# shield.net
KiCad netlist of a schematic drawn in EAGLE
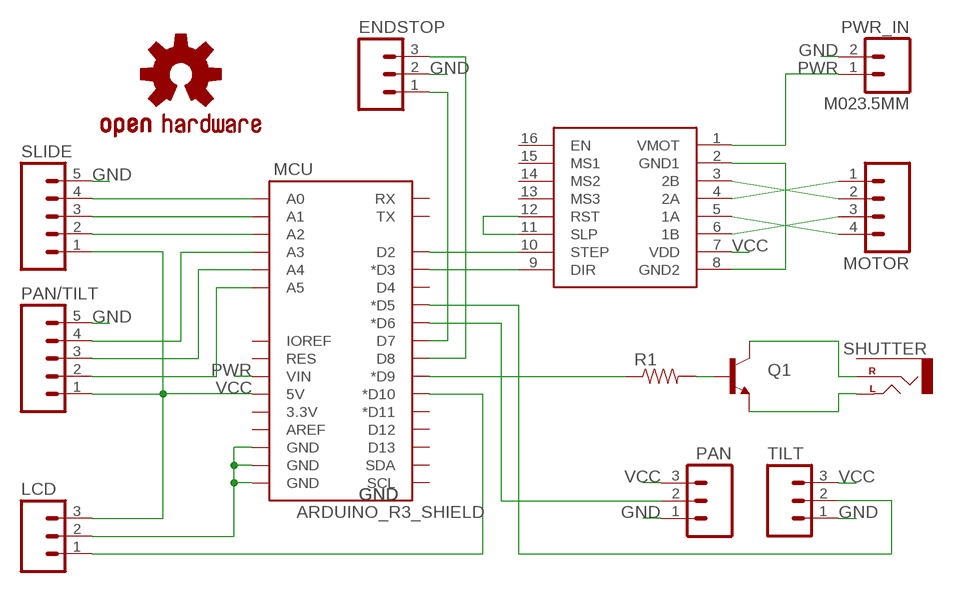
[diagram p0: schematic, sheet 1]

(export (version "E")
  (design (tool "Eeschema 10.0.6"))
  (components
    (comp (ref "ENDSTOP")
      (value "M03PTH")
      (footprint "eagle-import:1X03")
      (libsource (lib "eagle-import") (part "M03PTH"))
    )
    (comp (ref "LCD")
      (value "M03PTH")
      (footprint "eagle-import:1X03")
      (libsource (lib "eagle-import") (part "M03PTH"))
    )
    (comp (ref "LOGO1")
      (value "OSHW-LOGOM")
      (footprint "eagle-import:OSHW-LOGO-M")
      (libsource (lib "eagle-import") (part "OSHW-LOGOM"))
    )
    (comp (ref "MCU")
      (value "ARDUINO_R3_SHIELD")
      (footprint "eagle-import:UNO_R3_SHIELD")
      (libsource (lib "eagle-import") (part "ARDUINO_R3_SHIELD"))
    )
    (comp (ref "MOTOR")
      (value "M04POLAR")
      (footprint "eagle-import:MOLEX-1X4")
      (libsource (lib "eagle-import") (part "M04POLAR"))
    )
    (comp (ref "PAN")
      (value "M03PTH")
      (footprint "eagle-import:1X03")
      (libsource (lib "eagle-import") (part "M03PTH"))
    )
    (comp (ref "PAN/TILT")
      (value "M05PTH")
      (footprint "eagle-import:1X05")
      (libsource (lib "eagle-import") (part "M05PTH"))
    )
    (comp (ref "PWR_IN")
      (value "M023.5MM")
      (footprint "eagle-import:SCREWTERMINAL-3.5MM-2")
      (libsource (lib "eagle-import") (part "M023.5MM"))
    )
    (comp (ref "Q1")
      (value "TRANSISTOR_NPN2N3904")
      (footprint "eagle-import:TO-92")
      (libsource (lib "eagle-import") (part "TRANSISTOR_NPN2N3904"))
    )
    (comp (ref "R1")
      (value "RESISTORAXIAL-0.3")
      (footprint "eagle-import:AXIAL-0.3")
      (libsource (lib "eagle-import") (part "RESISTORAXIAL-0.3"))
    )
    (comp (ref "SHUTTER")
      (value "AUDIO-JACKPTH")
      (footprint "eagle-import:AUDIO-JACK")
      (libsource (lib "eagle-import") (part "AUDIO-JACKPTH"))
    )
    (comp (ref "SLIDE")
      (value "M05PTH")
      (footprint "eagle-import:1X05")
      (libsource (lib "eagle-import") (part "M05PTH"))
    )
    (comp (ref "SOCKET")
      (value "POLOLU DRIVER")
      (footprint "eagle-import:DIL16")
      (libsource (lib "eagle-import") (part "POLOLUESTEPPERDRIVER"))
    )
    (comp (ref "TILT")
      (value "M03PTH")
      (footprint "eagle-import:1X03")
      (libsource (lib "eagle-import") (part "M03PTH"))
    )
  )
  (nets
    (net (code "1") (name "/GND") (class "Default")
      (node (ref "ENDSTOP") (pin "2") (pinfunction "2_2") (pintype "passive"))
      (node (ref "LCD") (pin "2") (pinfunction "2_2") (pintype "passive"))
      (node (ref "MCU") (pin "GND@0") (pinfunction "GND_GND@0") (pintype "bidirectional"))
      (node (ref "MCU") (pin "GND@1") (pinfunction "GND_GND@1") (pintype "bidirectional"))
      (node (ref "MCU") (pin "GND@2") (pinfunction "GND_GND@2") (pintype "bidirectional"))
      (node (ref "PAN") (pin "1") (pinfunction "1_1") (pintype "passive"))
      (node (ref "PAN/TILT") (pin "5") (pinfunction "5_5") (pintype "passive"))
      (node (ref "PWR_IN") (pin "2") (pinfunction "2_2") (pintype "passive"))
      (node (ref "SLIDE") (pin "5") (pinfunction "5_5") (pintype "passive"))
      (node (ref "TILT") (pin "1") (pinfunction "1_1") (pintype "passive"))
    )
    (net (code "2") (name "/PWR") (class "Default")
      (node (ref "MCU") (pin "VIN") (pinfunction "VIN_VIN") (pintype "bidirectional"))
      (node (ref "PWR_IN") (pin "1") (pinfunction "1_1") (pintype "passive"))
      (node (ref "SOCKET") (pin "1") (pinfunction "VMOT_1") (pintype "power_in"))
    )
    (net (code "3") (name "/VCC") (class "Default")
      (node (ref "LCD") (pin "3") (pinfunction "3_3") (pintype "passive"))
      (node (ref "MCU") (pin "5V") (pinfunction "5V_5V") (pintype "bidirectional"))
      (node (ref "PAN") (pin "3") (pinfunction "3_3") (pintype "passive"))
      (node (ref "PAN/TILT") (pin "1") (pinfunction "1_1") (pintype "passive"))
      (node (ref "SLIDE") (pin "1") (pinfunction "1_1") (pintype "passive"))
      (node (ref "SOCKET") (pin "7") (pinfunction "VDD_7") (pintype "power_in"))
      (node (ref "TILT") (pin "3") (pinfunction "3_3") (pintype "passive"))
    )
    (net (code "4") (name "Net-(ENDSTOP-Pad1)") (class "Default")
      (node (ref "ENDSTOP") (pin "1") (pinfunction "1_1") (pintype "passive"))
      (node (ref "MCU") (pin "D7") (pinfunction "D7_D7") (pintype "bidirectional"))
    )
    (net (code "5") (name "Net-(ENDSTOP-Pad3)") (class "Default")
      (node (ref "ENDSTOP") (pin "3") (pinfunction "3_3") (pintype "passive"))
      (node (ref "MCU") (pin "D8") (pinfunction "D8_D8") (pintype "bidirectional"))
    )
    (net (code "6") (name "Net-(MCU-*D3)") (class "Default")
      (node (ref "MCU") (pin "D3") (pinfunction "*D3_D3") (pintype "bidirectional"))
      (node (ref "SOCKET") (pin "9") (pinfunction "DIR_9") (pintype "input"))
    )
    (net (code "7") (name "Net-(MCU-*D5)") (class "Default")
      (node (ref "MCU") (pin "D5") (pinfunction "*D5_D5") (pintype "bidirectional"))
      (node (ref "TILT") (pin "2") (pinfunction "2_2") (pintype "passive"))
    )
    (net (code "8") (name "Net-(MCU-*D6)") (class "Default")
      (node (ref "MCU") (pin "D6") (pinfunction "*D6_D6") (pintype "bidirectional"))
      (node (ref "PAN") (pin "2") (pinfunction "2_2") (pintype "passive"))
    )
    (net (code "9") (name "Net-(MCU-*D9)") (class "Default")
      (node (ref "MCU") (pin "D9") (pinfunction "*D9_D9") (pintype "bidirectional"))
      (node (ref "R1") (pin "P$1") (pinfunction "1_P$1") (pintype "passive"))
    )
    (net (code "10") (name "Net-(MCU-*D10)") (class "Default")
      (node (ref "LCD") (pin "1") (pinfunction "1_1") (pintype "passive"))
      (node (ref "MCU") (pin "D10") (pinfunction "*D10_D10") (pintype "bidirectional"))
    )
    (net (code "11") (name "Net-(MCU-PadA0)") (class "Default")
      (node (ref "MCU") (pin "A0") (pinfunction "A0_A0") (pintype "bidirectional"))
      (node (ref "SLIDE") (pin "4") (pinfunction "4_4") (pintype "passive"))
    )
    (net (code "12") (name "Net-(MCU-PadA1)") (class "Default")
      (node (ref "MCU") (pin "A1") (pinfunction "A1_A1") (pintype "bidirectional"))
      (node (ref "SLIDE") (pin "3") (pinfunction "3_3") (pintype "passive"))
    )
    (net (code "13") (name "Net-(MCU-PadA2)") (class "Default")
      (node (ref "MCU") (pin "A2") (pinfunction "A2_A2") (pintype "bidirectional"))
      (node (ref "SLIDE") (pin "2") (pinfunction "2_2") (pintype "passive"))
    )
    (net (code "14") (name "Net-(MCU-PadA3)") (class "Default")
      (node (ref "MCU") (pin "A3") (pinfunction "A3_A3") (pintype "bidirectional"))
      (node (ref "PAN/TILT") (pin "4") (pinfunction "4_4") (pintype "passive"))
    )
    (net (code "15") (name "Net-(MCU-PadA4)") (class "Default")
      (node (ref "MCU") (pin "A4") (pinfunction "A4_A4") (pintype "bidirectional"))
      (node (ref "PAN/TILT") (pin "3") (pinfunction "3_3") (pintype "passive"))
    )
    (net (code "16") (name "Net-(MCU-PadA5)") (class "Default")
      (node (ref "MCU") (pin "A5") (pinfunction "A5_A5") (pintype "bidirectional"))
      (node (ref "PAN/TILT") (pin "2") (pinfunction "2_2") (pintype "passive"))
    )
    (net (code "17") (name "Net-(Q1-B)") (class "Default")
      (node (ref "Q1") (pin "2") (pinfunction "B_2") (pintype "passive"))
      (node (ref "R1") (pin "P$2") (pinfunction "2_P$2") (pintype "passive"))
    )
    (net (code "18") (name "Net-(Q1-C)") (class "Default")
      (node (ref "Q1") (pin "3") (pinfunction "C_3") (pintype "passive"))
      (node (ref "SHUTTER") (pin "RING") (pinfunction "RIGHT_RING") (pintype "bidirectional"))
    )
    (net (code "19") (name "Net-(Q1-E)") (class "Default")
      (node (ref "Q1") (pin "1") (pinfunction "E_1") (pintype "passive"))
      (node (ref "SHUTTER") (pin "TIP") (pinfunction "LEFT_TIP") (pintype "bidirectional"))
    )
    (net (code "20") (name "Net-(SOCKET-1A)") (class "Default")
      (node (ref "MOTOR") (pin "4") (pinfunction "4_4") (pintype "passive"))
      (node (ref "SOCKET") (pin "5") (pinfunction "1A_5") (pintype "output"))
    )
    (net (code "21") (name "Net-(SOCKET-1B)") (class "Default")
      (node (ref "MOTOR") (pin "3") (pinfunction "3_3") (pintype "passive"))
      (node (ref "SOCKET") (pin "6") (pinfunction "1B_6") (pintype "output"))
    )
    (net (code "22") (name "Net-(SOCKET-2A)") (class "Default")
      (node (ref "MOTOR") (pin "1") (pinfunction "1_1") (pintype "passive"))
      (node (ref "SOCKET") (pin "4") (pinfunction "2A_4") (pintype "output"))
    )
    (net (code "23") (name "Net-(SOCKET-2B)") (class "Default")
      (node (ref "MOTOR") (pin "2") (pinfunction "2_2") (pintype "passive"))
      (node (ref "SOCKET") (pin "3") (pinfunction "2B_3") (pintype "output"))
    )
    (net (code "24") (name "Net-(SOCKET-GND1)") (class "Default")
      (node (ref "SOCKET") (pin "2") (pinfunction "GND1_2") (pintype "power_in"))
      (node (ref "SOCKET") (pin "8") (pinfunction "GND2_8") (pintype "power_in"))
    )
    (net (code "25") (name "Net-(SOCKET-RST)") (class "Default")
      (node (ref "SOCKET") (pin "11") (pinfunction "SLP_11") (pintype "input"))
      (node (ref "SOCKET") (pin "12") (pinfunction "RST_12") (pintype "input"))
    )
    (net (code "26") (name "Net-(SOCKET-STEP)") (class "Default")
      (node (ref "MCU") (pin "D2") (pinfunction "D2_D2") (pintype "bidirectional"))
      (node (ref "SOCKET") (pin "10") (pinfunction "STEP_10") (pintype "input"))
    )
    (net (code "27") (name "unconnected-(MCU-*D11-PadD11)") (class "Default")
      (node (ref "MCU") (pin "D11") (pinfunction "*D11_D11") (pintype "bidirectional"))
    )
    (net (code "28") (name "unconnected-(MCU-Pad3.3V)") (class "Default")
      (node (ref "MCU") (pin "3.3V") (pinfunction "3.3V_3.3V") (pintype "bidirectional"))
    )
    (net (code "29") (name "unconnected-(MCU-PadAREF)") (class "Default")
      (node (ref "MCU") (pin "AREF") (pinfunction "AREF_AREF") (pintype "bidirectional"))
    )
    (net (code "30") (name "unconnected-(MCU-PadD4)") (class "Default")
      (node (ref "MCU") (pin "D4") (pinfunction "D4_D4") (pintype "bidirectional"))
    )
    (net (code "31") (name "unconnected-(MCU-PadD12)") (class "Default")
      (node (ref "MCU") (pin "D12") (pinfunction "D12_D12") (pintype "bidirectional"))
    )
    (net (code "32") (name "unconnected-(MCU-PadD13)") (class "Default")
      (node (ref "MCU") (pin "D13") (pinfunction "D13_D13") (pintype "bidirectional"))
    )
    (net (code "33") (name "unconnected-(MCU-PadIOREF)") (class "Default")
      (node (ref "MCU") (pin "IOREF") (pinfunction "IOREF_IOREF") (pintype "bidirectional"))
    )
    (net (code "34") (name "unconnected-(MCU-PadRES)") (class "Default")
      (node (ref "MCU") (pin "RES") (pinfunction "RES_RES") (pintype "bidirectional"))
    )
    (net (code "35") (name "unconnected-(MCU-PadRX)") (class "Default")
      (node (ref "MCU") (pin "RX") (pinfunction "RX_RX") (pintype "bidirectional"))
    )
    (net (code "36") (name "unconnected-(MCU-PadSCL)") (class "Default")
      (node (ref "MCU") (pin "SCL") (pinfunction "SCL_SCL") (pintype "bidirectional"))
    )
    (net (code "37") (name "unconnected-(MCU-PadSDA)") (class "Default")
      (node (ref "MCU") (pin "SDA") (pinfunction "SDA_SDA") (pintype "bidirectional"))
    )
    (net (code "38") (name "unconnected-(MCU-PadTX)") (class "Default")
      (node (ref "MCU") (pin "TX") (pinfunction "TX_TX") (pintype "bidirectional"))
    )
    (net (code "39") (name "unconnected-(SHUTTER-PadSLEEVE)") (class "Default")
      (node (ref "SHUTTER") (pin "SLEEVE") (pinfunction "SLEEVE_SLEEVE") (pintype "bidirectional"))
    )
    (net (code "40") (name "unconnected-(SOCKET-EN-Pad16)") (class "Default")
      (node (ref "SOCKET") (pin "16") (pinfunction "EN_16") (pintype "input"))
    )
    (net (code "41") (name "unconnected-(SOCKET-MS1-Pad15)") (class "Default")
      (node (ref "SOCKET") (pin "15") (pinfunction "MS1_15") (pintype "input"))
    )
    (net (code "42") (name "unconnected-(SOCKET-MS2-Pad14)") (class "Default")
      (node (ref "SOCKET") (pin "14") (pinfunction "MS2_14") (pintype "input"))
    )
    (net (code "43") (name "unconnected-(SOCKET-MS3-Pad13)") (class "Default")
      (node (ref "SOCKET") (pin "13") (pinfunction "MS3_13") (pintype "input"))
    )
  )
)
